# ASM001-design-5.net
KiCad netlist of a schematic drawn in Altium Designer
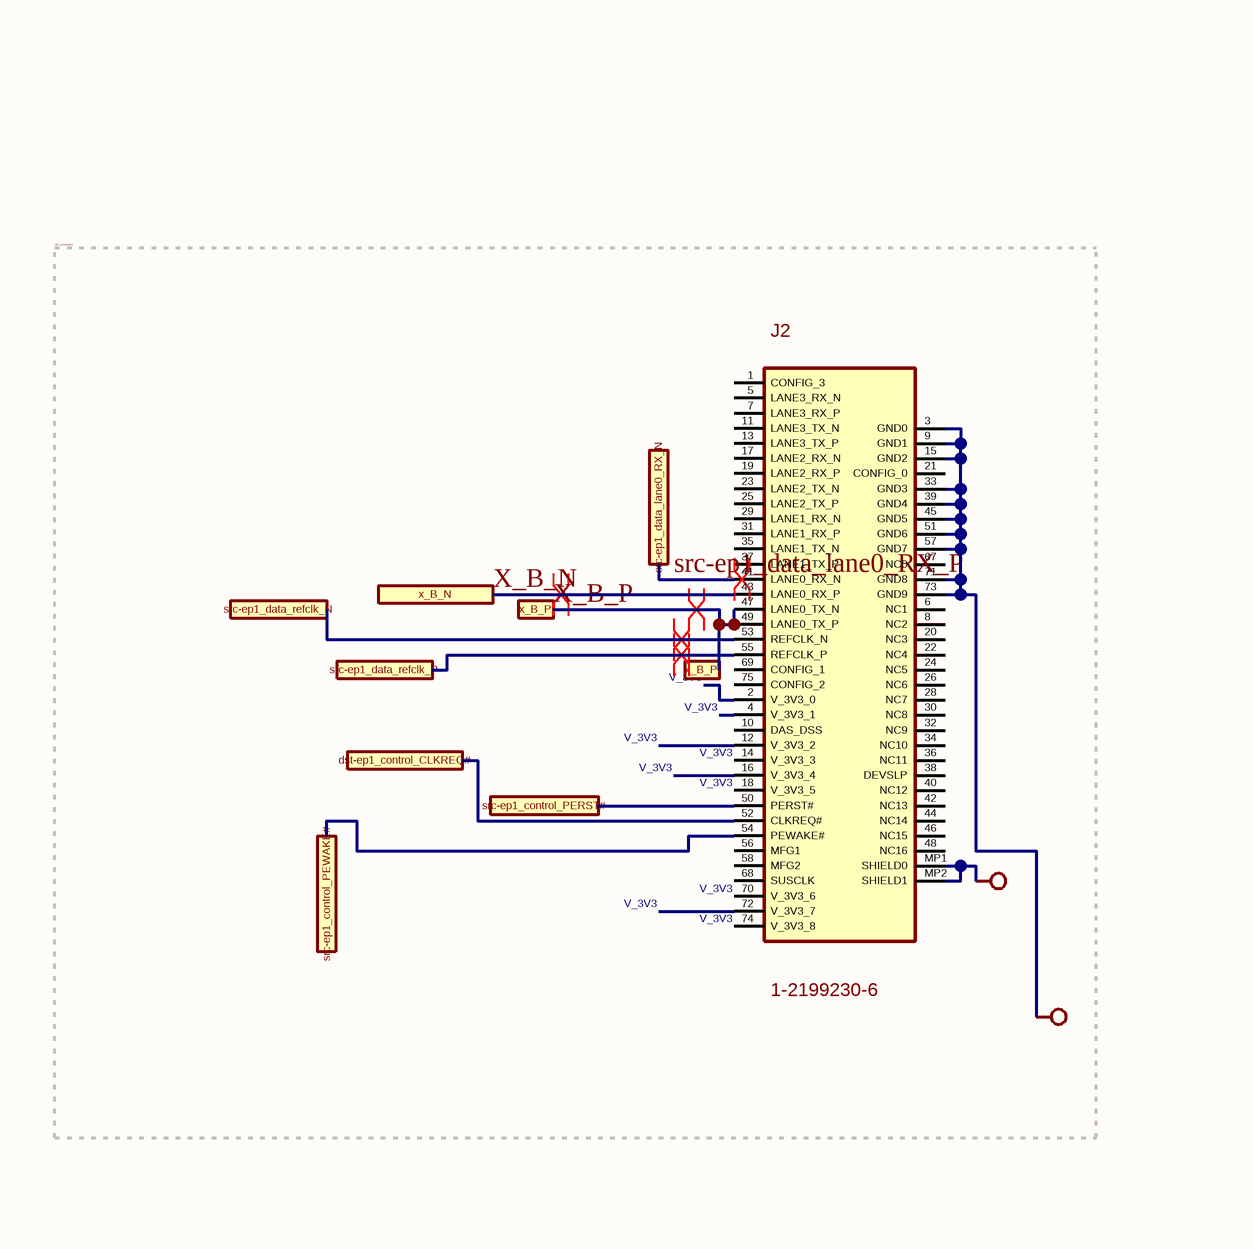
[diagram p0: ASM001-design-5.SchDoc, bottom column 2 of 4]
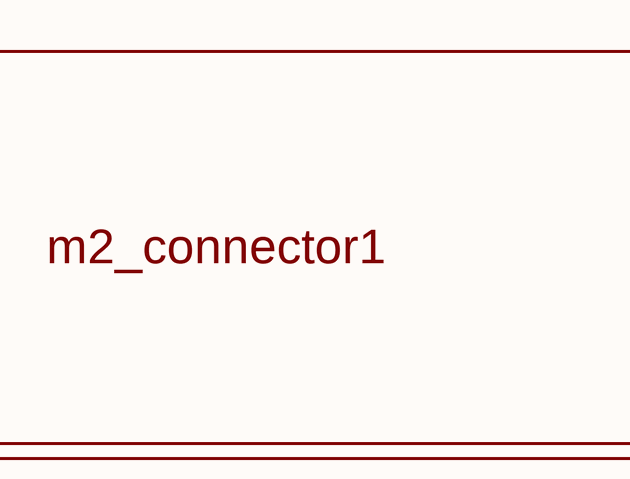
[diagram p1: ASM001-design-5.SchDoc, bottom column 4 of 4]

(export (version "E")
  (design (tool "Eeschema 10.0.6"))
  (components
    (comp (ref "J2")
      (value "1-2199230-6")
      (footprint "LP_1_2199230_6")
      (description "component")
      (fields
        (field (name "MANUFACTURER") "TE Connectivity")
        (field (name "DIGI-KEY_PART_NUMBER") "A118046TR-ND")
      )
      (libsource (lib "ASM001-design") (part "component"))
    )
  )
  (nets
    (net (code "1") (name "/V_3V3") (class "Default")
      (node (ref "J2") (pin "12") (pinfunction "V_3V3_2_12") (pintype "passive"))
      (node (ref "J2") (pin "14") (pinfunction "V_3V3_3_14") (pintype "passive"))
      (node (ref "J2") (pin "16") (pinfunction "V_3V3_4_16") (pintype "passive"))
      (node (ref "J2") (pin "18") (pinfunction "V_3V3_5_18") (pintype "passive"))
      (node (ref "J2") (pin "2") (pinfunction "V_3V3_0_2") (pintype "passive"))
      (node (ref "J2") (pin "4") (pinfunction "V_3V3_1_4") (pintype "passive"))
      (node (ref "J2") (pin "70") (pinfunction "V_3V3_6_70") (pintype "passive"))
      (node (ref "J2") (pin "72") (pinfunction "V_3V3_7_72") (pintype "passive"))
      (node (ref "J2") (pin "74") (pinfunction "V_3V3_8_74") (pintype "passive"))
    )
    (net (code "2") (name "/X_B_N") (class "Default")
      (node (ref "J2") (pin "43") (pinfunction "LANE0_RX_P_43") (pintype "passive"))
    )
    (net (code "3") (name "/X_B_P") (class "Default")
      (node (ref "J2") (pin "47") (pinfunction "LANE0_TX_N_47") (pintype "passive"))
      (node (ref "J2") (pin "49") (pinfunction "LANE0_TX_P_49") (pintype "passive"))
    )
    (net (code "4") (name "/dst-ep1_control_CLKREQ#") (class "Default")
      (node (ref "J2") (pin "52") (pinfunction "CLKREQ#_52") (pintype "passive"))
    )
    (net (code "5") (name "/src-ep1_control_PERST#") (class "Default")
      (node (ref "J2") (pin "50") (pinfunction "PERST#_50") (pintype "passive"))
    )
    (net (code "6") (name "/src-ep1_control_PEWAKE#") (class "Default")
      (node (ref "J2") (pin "54") (pinfunction "PEWAKE#_54") (pintype "passive"))
    )
    (net (code "7") (name "/src-ep1_data_lane0_RX_P") (class "Default")
      (node (ref "J2") (pin "41") (pinfunction "LANE0_RX_N_41") (pintype "passive"))
    )
    (net (code "8") (name "/src-ep1_data_refclk_N") (class "Default")
      (node (ref "J2") (pin "53") (pinfunction "REFCLK_N_53") (pintype "passive"))
    )
    (net (code "9") (name "/src-ep1_data_refclk_P") (class "Default")
      (node (ref "J2") (pin "55") (pinfunction "REFCLK_P_55") (pintype "passive"))
    )
    (net (code "10") (name "<NO NET>") (class "Default")
      (node (ref "J2") (pin "15") (pinfunction "GND2_15") (pintype "passive"))
      (node (ref "J2") (pin "3") (pinfunction "GND0_3") (pintype "passive"))
      (node (ref "J2") (pin "33") (pinfunction "GND3_33") (pintype "passive"))
      (node (ref "J2") (pin "39") (pinfunction "GND4_39") (pintype "passive"))
      (node (ref "J2") (pin "45") (pinfunction "GND5_45") (pintype "passive"))
      (node (ref "J2") (pin "51") (pinfunction "GND6_51") (pintype "passive"))
      (node (ref "J2") (pin "57") (pinfunction "GND7_57") (pintype "passive"))
      (node (ref "J2") (pin "71") (pinfunction "GND8_71") (pintype "passive"))
      (node (ref "J2") (pin "73") (pinfunction "GND9_73") (pintype "passive"))
      (node (ref "J2") (pin "9") (pinfunction "GND1_9") (pintype "passive"))
      (node (ref "J2") (pin "MP1") (pinfunction "SHIELD0_MP1") (pintype "passive"))
      (node (ref "J2") (pin "MP2") (pinfunction "SHIELD1_MP2") (pintype "passive"))
    )
    (net (code "11") (name "unconnected-(J2-CONFIG_0-Pad21)") (class "Default")
      (node (ref "J2") (pin "21") (pinfunction "CONFIG_0_21") (pintype "passive"))
    )
    (net (code "12") (name "unconnected-(J2-CONFIG_1-Pad69)") (class "Default")
      (node (ref "J2") (pin "69") (pinfunction "CONFIG_1_69") (pintype "passive"))
    )
    (net (code "13") (name "unconnected-(J2-CONFIG_2-Pad75)") (class "Default")
      (node (ref "J2") (pin "75") (pinfunction "CONFIG_2_75") (pintype "passive"))
    )
    (net (code "14") (name "unconnected-(J2-CONFIG_3-Pad1)") (class "Default")
      (node (ref "J2") (pin "1") (pinfunction "CONFIG_3_1") (pintype "passive"))
    )
    (net (code "15") (name "unconnected-(J2-DAS_DSS-Pad10)") (class "Default")
      (node (ref "J2") (pin "10") (pinfunction "DAS_DSS_10") (pintype "passive"))
    )
    (net (code "16") (name "unconnected-(J2-DEVSLP-Pad38)") (class "Default")
      (node (ref "J2") (pin "38") (pinfunction "DEVSLP_38") (pintype "passive"))
    )
    (net (code "17") (name "unconnected-(J2-LANE1_RX_N-Pad29)") (class "Default")
      (node (ref "J2") (pin "29") (pinfunction "LANE1_RX_N_29") (pintype "passive"))
    )
    (net (code "18") (name "unconnected-(J2-LANE1_RX_P-Pad31)") (class "Default")
      (node (ref "J2") (pin "31") (pinfunction "LANE1_RX_P_31") (pintype "passive"))
    )
    (net (code "19") (name "unconnected-(J2-LANE1_TX_N-Pad35)") (class "Default")
      (node (ref "J2") (pin "35") (pinfunction "LANE1_TX_N_35") (pintype "passive"))
    )
    (net (code "20") (name "unconnected-(J2-LANE1_TX_P-Pad37)") (class "Default")
      (node (ref "J2") (pin "37") (pinfunction "LANE1_TX_P_37") (pintype "passive"))
    )
    (net (code "21") (name "unconnected-(J2-LANE2_RX_N-Pad17)") (class "Default")
      (node (ref "J2") (pin "17") (pinfunction "LANE2_RX_N_17") (pintype "passive"))
    )
    (net (code "22") (name "unconnected-(J2-LANE2_RX_P-Pad19)") (class "Default")
      (node (ref "J2") (pin "19") (pinfunction "LANE2_RX_P_19") (pintype "passive"))
    )
    (net (code "23") (name "unconnected-(J2-LANE2_TX_N-Pad23)") (class "Default")
      (node (ref "J2") (pin "23") (pinfunction "LANE2_TX_N_23") (pintype "passive"))
    )
    (net (code "24") (name "unconnected-(J2-LANE2_TX_P-Pad25)") (class "Default")
      (node (ref "J2") (pin "25") (pinfunction "LANE2_TX_P_25") (pintype "passive"))
    )
    (net (code "25") (name "unconnected-(J2-LANE3_RX_N-Pad5)") (class "Default")
      (node (ref "J2") (pin "5") (pinfunction "LANE3_RX_N_5") (pintype "passive"))
    )
    (net (code "26") (name "unconnected-(J2-LANE3_RX_P-Pad7)") (class "Default")
      (node (ref "J2") (pin "7") (pinfunction "LANE3_RX_P_7") (pintype "passive"))
    )
    (net (code "27") (name "unconnected-(J2-LANE3_TX_N-Pad11)") (class "Default")
      (node (ref "J2") (pin "11") (pinfunction "LANE3_TX_N_11") (pintype "passive"))
    )
    (net (code "28") (name "unconnected-(J2-LANE3_TX_P-Pad13)") (class "Default")
      (node (ref "J2") (pin "13") (pinfunction "LANE3_TX_P_13") (pintype "passive"))
    )
    (net (code "29") (name "unconnected-(J2-MFG1-Pad56)") (class "Default")
      (node (ref "J2") (pin "56") (pinfunction "MFG1_56") (pintype "passive"))
    )
    (net (code "30") (name "unconnected-(J2-MFG2-Pad58)") (class "Default")
      (node (ref "J2") (pin "58") (pinfunction "MFG2_58") (pintype "passive"))
    )
    (net (code "31") (name "unconnected-(J2-NC0-Pad67)") (class "Default")
      (node (ref "J2") (pin "67") (pinfunction "NC0_67") (pintype "passive"))
    )
    (net (code "32") (name "unconnected-(J2-NC1-Pad6)") (class "Default")
      (node (ref "J2") (pin "6") (pinfunction "NC1_6") (pintype "passive"))
    )
    (net (code "33") (name "unconnected-(J2-NC2-Pad8)") (class "Default")
      (node (ref "J2") (pin "8") (pinfunction "NC2_8") (pintype "passive"))
    )
    (net (code "34") (name "unconnected-(J2-NC3-Pad20)") (class "Default")
      (node (ref "J2") (pin "20") (pinfunction "NC3_20") (pintype "passive"))
    )
    (net (code "35") (name "unconnected-(J2-NC4-Pad22)") (class "Default")
      (node (ref "J2") (pin "22") (pinfunction "NC4_22") (pintype "passive"))
    )
    (net (code "36") (name "unconnected-(J2-NC5-Pad24)") (class "Default")
      (node (ref "J2") (pin "24") (pinfunction "NC5_24") (pintype "passive"))
    )
    (net (code "37") (name "unconnected-(J2-NC6-Pad26)") (class "Default")
      (node (ref "J2") (pin "26") (pinfunction "NC6_26") (pintype "passive"))
    )
    (net (code "38") (name "unconnected-(J2-NC7-Pad28)") (class "Default")
      (node (ref "J2") (pin "28") (pinfunction "NC7_28") (pintype "passive"))
    )
    (net (code "39") (name "unconnected-(J2-NC8-Pad30)") (class "Default")
      (node (ref "J2") (pin "30") (pinfunction "NC8_30") (pintype "passive"))
    )
    (net (code "40") (name "unconnected-(J2-NC9-Pad32)") (class "Default")
      (node (ref "J2") (pin "32") (pinfunction "NC9_32") (pintype "passive"))
    )
    (net (code "41") (name "unconnected-(J2-NC10-Pad34)") (class "Default")
      (node (ref "J2") (pin "34") (pinfunction "NC10_34") (pintype "passive"))
    )
    (net (code "42") (name "unconnected-(J2-NC11-Pad36)") (class "Default")
      (node (ref "J2") (pin "36") (pinfunction "NC11_36") (pintype "passive"))
    )
    (net (code "43") (name "unconnected-(J2-NC12-Pad40)") (class "Default")
      (node (ref "J2") (pin "40") (pinfunction "NC12_40") (pintype "passive"))
    )
    (net (code "44") (name "unconnected-(J2-NC13-Pad42)") (class "Default")
      (node (ref "J2") (pin "42") (pinfunction "NC13_42") (pintype "passive"))
    )
    (net (code "45") (name "unconnected-(J2-NC14-Pad44)") (class "Default")
      (node (ref "J2") (pin "44") (pinfunction "NC14_44") (pintype "passive"))
    )
    (net (code "46") (name "unconnected-(J2-NC15-Pad46)") (class "Default")
      (node (ref "J2") (pin "46") (pinfunction "NC15_46") (pintype "passive"))
    )
    (net (code "47") (name "unconnected-(J2-NC16-Pad48)") (class "Default")
      (node (ref "J2") (pin "48") (pinfunction "NC16_48") (pintype "passive"))
    )
    (net (code "48") (name "unconnected-(J2-SUSCLK-Pad68)") (class "Default")
      (node (ref "J2") (pin "68") (pinfunction "SUSCLK_68") (pintype "passive"))
    )
  )
)
